# gt-jtx-m32-ver1_0.net
KiCad netlist of a schematic drawn in EAGLE
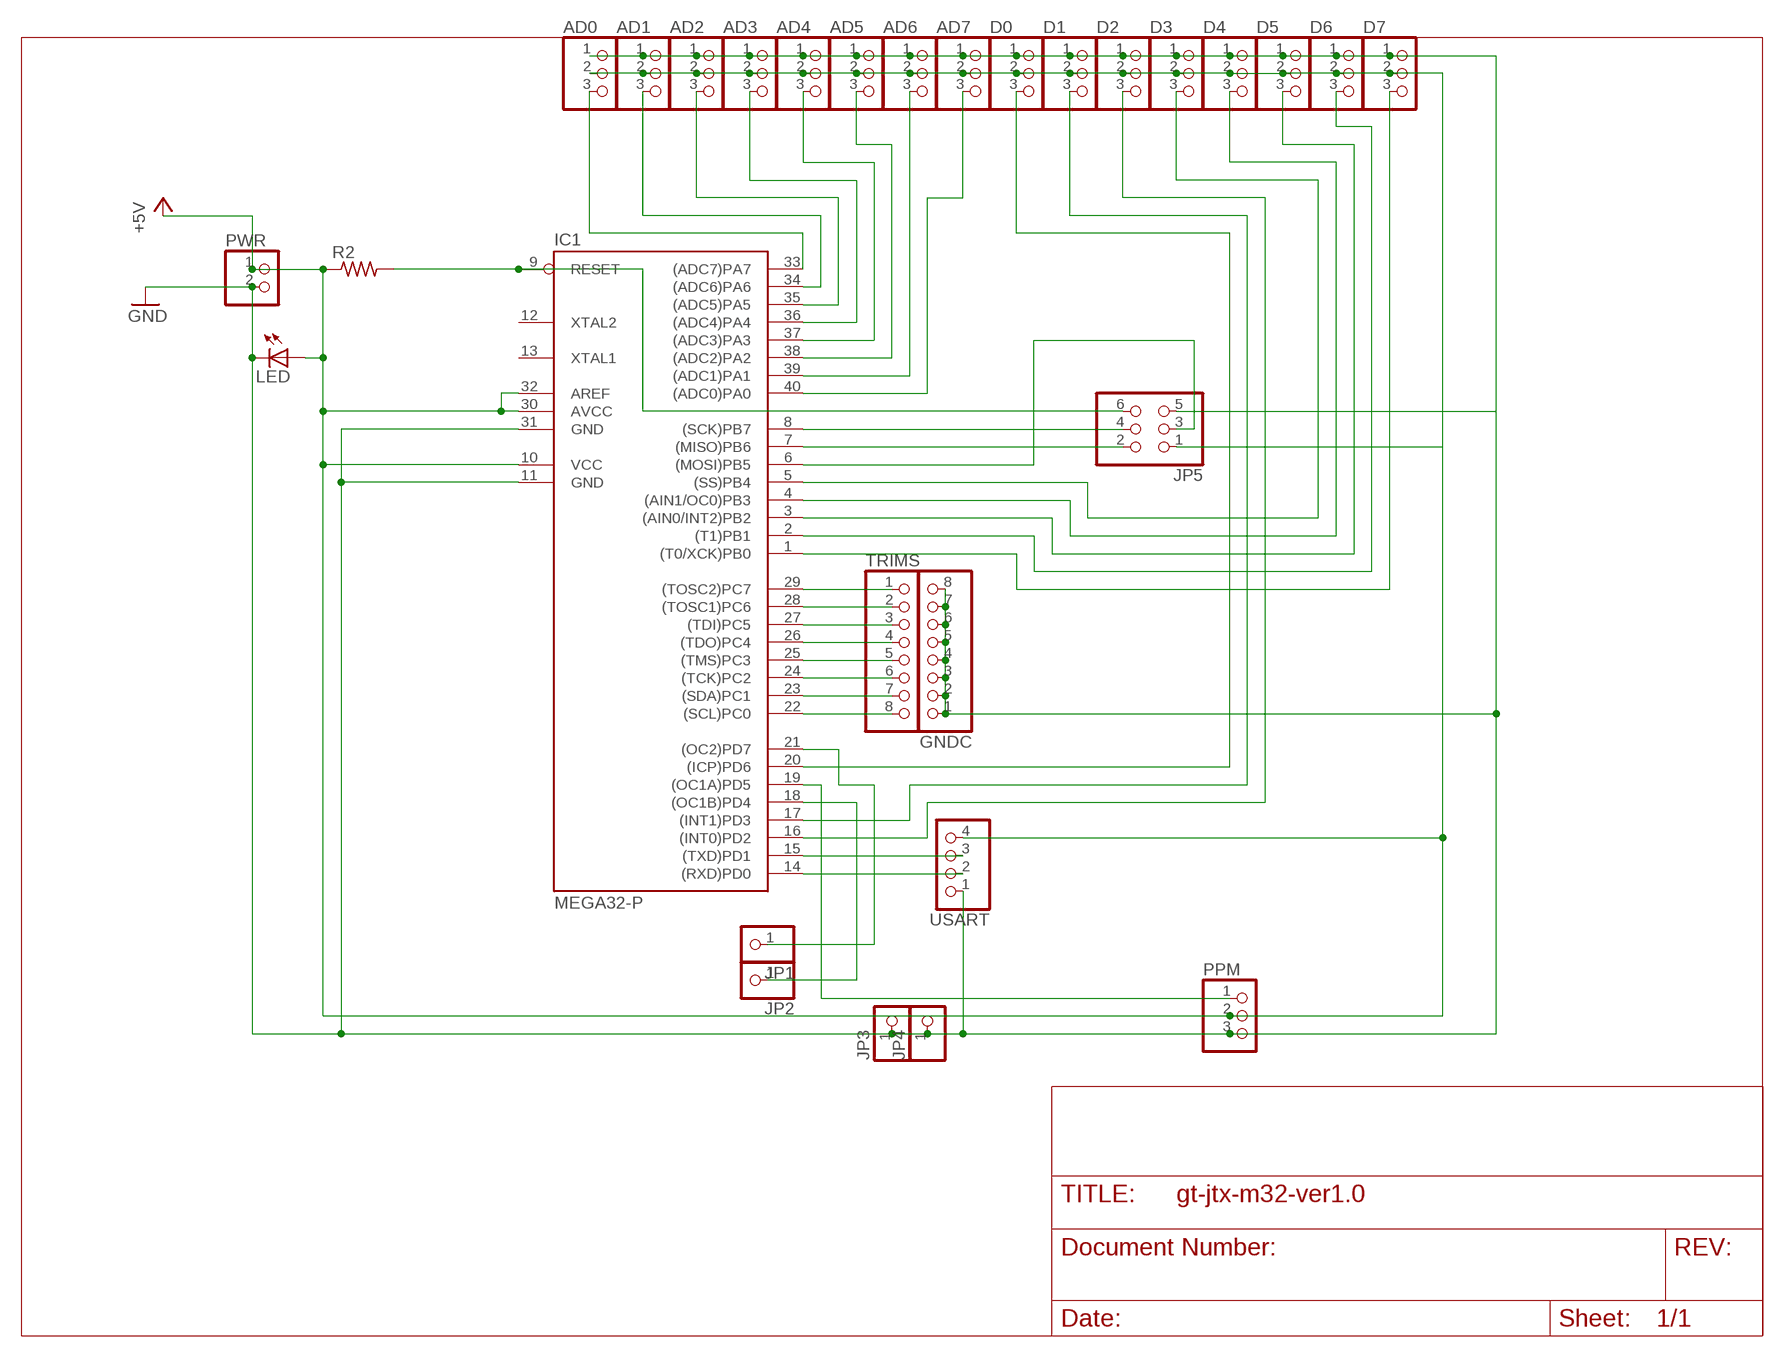
[diagram p0: schematic, sheet 1]

(export (version "E")
  (design (tool "Eeschema 10.0.6"))
  (components
    (comp (ref "AD0")
      (value "PINHD-1X3")
      (footprint "eagle-import:1X03")
      (libsource (lib "eagle-import") (part "PINHD-1X3"))
    )
    (comp (ref "AD1")
      (value "PINHD-1X3")
      (footprint "eagle-import:1X03")
      (libsource (lib "eagle-import") (part "PINHD-1X3"))
    )
    (comp (ref "AD2")
      (value "PINHD-1X3")
      (footprint "eagle-import:1X03")
      (libsource (lib "eagle-import") (part "PINHD-1X3"))
    )
    (comp (ref "AD3")
      (value "PINHD-1X3")
      (footprint "eagle-import:1X03")
      (libsource (lib "eagle-import") (part "PINHD-1X3"))
    )
    (comp (ref "AD4")
      (value "PINHD-1X3")
      (footprint "eagle-import:1X03")
      (libsource (lib "eagle-import") (part "PINHD-1X3"))
    )
    (comp (ref "AD5")
      (value "PINHD-1X3")
      (footprint "eagle-import:1X03")
      (libsource (lib "eagle-import") (part "PINHD-1X3"))
    )
    (comp (ref "AD6")
      (value "PINHD-1X3")
      (footprint "eagle-import:1X03")
      (libsource (lib "eagle-import") (part "PINHD-1X3"))
    )
    (comp (ref "AD7")
      (value "PINHD-1X3")
      (footprint "eagle-import:1X03")
      (libsource (lib "eagle-import") (part "PINHD-1X3"))
    )
    (comp (ref "D0")
      (value "PINHD-1X3")
      (footprint "eagle-import:1X03")
      (libsource (lib "eagle-import") (part "PINHD-1X3"))
    )
    (comp (ref "D1")
      (value "PINHD-1X3")
      (footprint "eagle-import:1X03")
      (libsource (lib "eagle-import") (part "PINHD-1X3"))
    )
    (comp (ref "D2")
      (value "PINHD-1X3")
      (footprint "eagle-import:1X03")
      (libsource (lib "eagle-import") (part "PINHD-1X3"))
    )
    (comp (ref "D3")
      (value "PINHD-1X3")
      (footprint "eagle-import:1X03")
      (libsource (lib "eagle-import") (part "PINHD-1X3"))
    )
    (comp (ref "D4")
      (value "PINHD-1X3")
      (footprint "eagle-import:1X03")
      (libsource (lib "eagle-import") (part "PINHD-1X3"))
    )
    (comp (ref "D5")
      (value "PINHD-1X3")
      (footprint "eagle-import:1X03")
      (libsource (lib "eagle-import") (part "PINHD-1X3"))
    )
    (comp (ref "D6")
      (value "PINHD-1X3")
      (footprint "eagle-import:1X03")
      (libsource (lib "eagle-import") (part "PINHD-1X3"))
    )
    (comp (ref "D7")
      (value "PINHD-1X3")
      (footprint "eagle-import:1X03")
      (libsource (lib "eagle-import") (part "PINHD-1X3"))
    )
    (comp (ref "GNDC")
      (value "PINHD-1X8")
      (footprint "eagle-import:1X08")
      (libsource (lib "eagle-import") (part "PINHD-1X8"))
    )
    (comp (ref "IC1")
      (value "MEGA32-P")
      (footprint "eagle-import:DIL40")
      (fields (field (name "MPN") "ATMEGA32-16PU"))
      (libsource (lib "eagle-import") (part "MEGA32-P"))
    )
    (comp (ref "JP1")
      (value "PINHD-1X1")
      (footprint "eagle-import:1X01")
      (libsource (lib "eagle-import") (part "PINHD-1X1"))
    )
    (comp (ref "JP2")
      (value "PINHD-1X1")
      (footprint "eagle-import:1X01")
      (libsource (lib "eagle-import") (part "PINHD-1X1"))
    )
    (comp (ref "JP3")
      (value "PINHD-1X1")
      (footprint "eagle-import:1X01")
      (libsource (lib "eagle-import") (part "PINHD-1X1"))
    )
    (comp (ref "JP4")
      (value "PINHD-1X1")
      (footprint "eagle-import:1X01")
      (libsource (lib "eagle-import") (part "PINHD-1X1"))
    )
    (comp (ref "JP5")
      (value "PINHD-2X3")
      (footprint "eagle-import:2X03")
      (libsource (lib "eagle-import") (part "PINHD-2X3"))
    )
    (comp (ref "LED")
      (value "LED5MM")
      (footprint "eagle-import:LED5MM")
      (libsource (lib "eagle-import") (part "LED5MM"))
    )
    (comp (ref "PPM")
      (value "PINHD-1X3")
      (footprint "eagle-import:1X03")
      (libsource (lib "eagle-import") (part "PINHD-1X3"))
    )
    (comp (ref "PWR")
      (value "PINHD-1X2")
      (footprint "eagle-import:1X02")
      (libsource (lib "eagle-import") (part "PINHD-1X2"))
    )
    (comp (ref "R2")
      (value "R-US_0204/2V")
      (footprint "eagle-import:0204V")
      (libsource (lib "eagle-import") (part "R-US_0204/2V"))
    )
    (comp (ref "TRIMS")
      (value "PINHD-1X8")
      (footprint "eagle-import:1X08")
      (libsource (lib "eagle-import") (part "PINHD-1X8"))
    )
    (comp (ref "USART")
      (value "PINHD-1X4")
      (footprint "eagle-import:1X04")
      (libsource (lib "eagle-import") (part "PINHD-1X4"))
    )
  )
  (nets
    (net (code "1") (name "+5V") (class "Default")
      (node (ref "AD0") (pin "2") (pinfunction "2_2") (pintype "passive"))
      (node (ref "AD1") (pin "2") (pinfunction "2_2") (pintype "passive"))
      (node (ref "AD2") (pin "2") (pinfunction "2_2") (pintype "passive"))
      (node (ref "AD3") (pin "2") (pinfunction "2_2") (pintype "passive"))
      (node (ref "AD4") (pin "2") (pinfunction "2_2") (pintype "passive"))
      (node (ref "AD5") (pin "2") (pinfunction "2_2") (pintype "passive"))
      (node (ref "AD6") (pin "2") (pinfunction "2_2") (pintype "passive"))
      (node (ref "AD7") (pin "2") (pinfunction "2_2") (pintype "passive"))
      (node (ref "D0") (pin "2") (pinfunction "2_2") (pintype "passive"))
      (node (ref "D1") (pin "2") (pinfunction "2_2") (pintype "passive"))
      (node (ref "D2") (pin "2") (pinfunction "2_2") (pintype "passive"))
      (node (ref "D3") (pin "2") (pinfunction "2_2") (pintype "passive"))
      (node (ref "D4") (pin "2") (pinfunction "2_2") (pintype "passive"))
      (node (ref "D5") (pin "2") (pinfunction "2_2") (pintype "passive"))
      (node (ref "D6") (pin "2") (pinfunction "2_2") (pintype "passive"))
      (node (ref "D7") (pin "2") (pinfunction "2_2") (pintype "passive"))
      (node (ref "IC1") (pin "10") (pinfunction "VCC_10") (pintype "power_in"))
      (node (ref "IC1") (pin "30") (pinfunction "AVCC_30") (pintype "power_in"))
      (node (ref "IC1") (pin "32") (pinfunction "AREF_32") (pintype "passive"))
      (node (ref "JP5") (pin "1") (pinfunction "1_1") (pintype "passive"))
      (node (ref "LED") (pin "A") (pinfunction "A_A") (pintype "passive"))
      (node (ref "PPM") (pin "2") (pinfunction "2_2") (pintype "passive"))
      (node (ref "PWR") (pin "1") (pinfunction "1_1") (pintype "passive"))
      (node (ref "R2") (pin "1") (pinfunction "1_1") (pintype "passive"))
      (node (ref "USART") (pin "4") (pinfunction "4_4") (pintype "passive"))
    )
    (net (code "2") (name "GND") (class "Default")
      (node (ref "AD0") (pin "1") (pinfunction "1_1") (pintype "passive"))
      (node (ref "AD1") (pin "1") (pinfunction "1_1") (pintype "passive"))
      (node (ref "AD2") (pin "1") (pinfunction "1_1") (pintype "passive"))
      (node (ref "AD3") (pin "1") (pinfunction "1_1") (pintype "passive"))
      (node (ref "AD4") (pin "1") (pinfunction "1_1") (pintype "passive"))
      (node (ref "AD5") (pin "1") (pinfunction "1_1") (pintype "passive"))
      (node (ref "AD6") (pin "1") (pinfunction "1_1") (pintype "passive"))
      (node (ref "AD7") (pin "1") (pinfunction "1_1") (pintype "passive"))
      (node (ref "D0") (pin "1") (pinfunction "1_1") (pintype "passive"))
      (node (ref "D1") (pin "1") (pinfunction "1_1") (pintype "passive"))
      (node (ref "D2") (pin "1") (pinfunction "1_1") (pintype "passive"))
      (node (ref "D3") (pin "1") (pinfunction "1_1") (pintype "passive"))
      (node (ref "D4") (pin "1") (pinfunction "1_1") (pintype "passive"))
      (node (ref "D5") (pin "1") (pinfunction "1_1") (pintype "passive"))
      (node (ref "D6") (pin "1") (pinfunction "1_1") (pintype "passive"))
      (node (ref "D7") (pin "1") (pinfunction "1_1") (pintype "passive"))
      (node (ref "GNDC") (pin "1") (pinfunction "1_1") (pintype "passive"))
      (node (ref "GNDC") (pin "2") (pinfunction "2_2") (pintype "passive"))
      (node (ref "GNDC") (pin "3") (pinfunction "3_3") (pintype "passive"))
      (node (ref "GNDC") (pin "4") (pinfunction "4_4") (pintype "passive"))
      (node (ref "GNDC") (pin "5") (pinfunction "5_5") (pintype "passive"))
      (node (ref "GNDC") (pin "6") (pinfunction "6_6") (pintype "passive"))
      (node (ref "GNDC") (pin "7") (pinfunction "7_7") (pintype "passive"))
      (node (ref "GNDC") (pin "8") (pinfunction "8_8") (pintype "passive"))
      (node (ref "IC1") (pin "11") (pinfunction "GND_11") (pintype "power_in"))
      (node (ref "IC1") (pin "31") (pinfunction "GND_31") (pintype "power_in"))
      (node (ref "JP3") (pin "1") (pinfunction "1_1") (pintype "passive"))
      (node (ref "JP4") (pin "1") (pinfunction "1_1") (pintype "passive"))
      (node (ref "JP5") (pin "5") (pinfunction "5_5") (pintype "passive"))
      (node (ref "LED") (pin "K") (pinfunction "C_K") (pintype "passive"))
      (node (ref "PPM") (pin "3") (pinfunction "3_3") (pintype "passive"))
      (node (ref "PWR") (pin "2") (pinfunction "2_2") (pintype "passive"))
      (node (ref "USART") (pin "1") (pinfunction "1_1") (pintype "passive"))
    )
    (net (code "3") (name "Net-(IC1-(ADC0)PA0)") (class "Default")
      (node (ref "AD7") (pin "3") (pinfunction "3_3") (pintype "passive"))
      (node (ref "IC1") (pin "40") (pinfunction "(ADC0)PA0_40") (pintype "bidirectional"))
    )
    (net (code "4") (name "Net-(IC1-(ADC1)PA1)") (class "Default")
      (node (ref "AD6") (pin "3") (pinfunction "3_3") (pintype "passive"))
      (node (ref "IC1") (pin "39") (pinfunction "(ADC1)PA1_39") (pintype "bidirectional"))
    )
    (net (code "5") (name "Net-(IC1-(ADC2)PA2)") (class "Default")
      (node (ref "AD5") (pin "3") (pinfunction "3_3") (pintype "passive"))
      (node (ref "IC1") (pin "38") (pinfunction "(ADC2)PA2_38") (pintype "bidirectional"))
    )
    (net (code "6") (name "Net-(IC1-(ADC3)PA3)") (class "Default")
      (node (ref "AD4") (pin "3") (pinfunction "3_3") (pintype "passive"))
      (node (ref "IC1") (pin "37") (pinfunction "(ADC3)PA3_37") (pintype "bidirectional"))
    )
    (net (code "7") (name "Net-(IC1-(ADC4)PA4)") (class "Default")
      (node (ref "AD3") (pin "3") (pinfunction "3_3") (pintype "passive"))
      (node (ref "IC1") (pin "36") (pinfunction "(ADC4)PA4_36") (pintype "bidirectional"))
    )
    (net (code "8") (name "Net-(IC1-(ADC5)PA5)") (class "Default")
      (node (ref "AD2") (pin "3") (pinfunction "3_3") (pintype "passive"))
      (node (ref "IC1") (pin "35") (pinfunction "(ADC5)PA5_35") (pintype "bidirectional"))
    )
    (net (code "9") (name "Net-(IC1-(ADC6)PA6)") (class "Default")
      (node (ref "AD1") (pin "3") (pinfunction "3_3") (pintype "passive"))
      (node (ref "IC1") (pin "34") (pinfunction "(ADC6)PA6_34") (pintype "bidirectional"))
    )
    (net (code "10") (name "Net-(IC1-(ADC7)PA7)") (class "Default")
      (node (ref "AD0") (pin "3") (pinfunction "3_3") (pintype "passive"))
      (node (ref "IC1") (pin "33") (pinfunction "(ADC7)PA7_33") (pintype "bidirectional"))
    )
    (net (code "11") (name "Net-(IC1-(AIN0{slash}INT2)PB2)") (class "Default")
      (node (ref "D5") (pin "3") (pinfunction "3_3") (pintype "passive"))
      (node (ref "IC1") (pin "3") (pinfunction "(AIN0/INT2)PB2_3") (pintype "bidirectional"))
    )
    (net (code "12") (name "Net-(IC1-(AIN1{slash}OC0)PB3)") (class "Default")
      (node (ref "D4") (pin "3") (pinfunction "3_3") (pintype "passive"))
      (node (ref "IC1") (pin "4") (pinfunction "(AIN1/OC0)PB3_4") (pintype "bidirectional"))
    )
    (net (code "13") (name "Net-(IC1-(ICP)PD6)") (class "Default")
      (node (ref "D0") (pin "3") (pinfunction "3_3") (pintype "passive"))
      (node (ref "IC1") (pin "20") (pinfunction "(ICP)PD6_20") (pintype "bidirectional"))
    )
    (net (code "14") (name "Net-(IC1-(INT0)PD2)") (class "Default")
      (node (ref "D2") (pin "3") (pinfunction "3_3") (pintype "passive"))
      (node (ref "IC1") (pin "16") (pinfunction "(INT0)PD2_16") (pintype "bidirectional"))
    )
    (net (code "15") (name "Net-(IC1-(INT1)PD3)") (class "Default")
      (node (ref "D1") (pin "3") (pinfunction "3_3") (pintype "passive"))
      (node (ref "IC1") (pin "17") (pinfunction "(INT1)PD3_17") (pintype "bidirectional"))
    )
    (net (code "16") (name "Net-(IC1-(MISO)PB6)") (class "Default")
      (node (ref "IC1") (pin "7") (pinfunction "(MISO)PB6_7") (pintype "bidirectional"))
      (node (ref "JP5") (pin "2") (pinfunction "2_2") (pintype "passive"))
    )
    (net (code "17") (name "Net-(IC1-(MOSI)PB5)") (class "Default")
      (node (ref "IC1") (pin "6") (pinfunction "(MOSI)PB5_6") (pintype "bidirectional"))
      (node (ref "JP5") (pin "3") (pinfunction "3_3") (pintype "passive"))
    )
    (net (code "18") (name "Net-(IC1-(OC1A)PD5)") (class "Default")
      (node (ref "IC1") (pin "19") (pinfunction "(OC1A)PD5_19") (pintype "bidirectional"))
      (node (ref "PPM") (pin "1") (pinfunction "1_1") (pintype "passive"))
    )
    (net (code "19") (name "Net-(IC1-(OC1B)PD4)") (class "Default")
      (node (ref "IC1") (pin "18") (pinfunction "(OC1B)PD4_18") (pintype "bidirectional"))
      (node (ref "JP2") (pin "1") (pinfunction "1_1") (pintype "passive"))
    )
    (net (code "20") (name "Net-(IC1-(OC2)PD7)") (class "Default")
      (node (ref "IC1") (pin "21") (pinfunction "(OC2)PD7_21") (pintype "bidirectional"))
      (node (ref "JP1") (pin "1") (pinfunction "1_1") (pintype "passive"))
    )
    (net (code "21") (name "Net-(IC1-(RXD)PD0)") (class "Default")
      (node (ref "IC1") (pin "14") (pinfunction "(RXD)PD0_14") (pintype "bidirectional"))
      (node (ref "USART") (pin "2") (pinfunction "2_2") (pintype "passive"))
    )
    (net (code "22") (name "Net-(IC1-(SCK)PB7)") (class "Default")
      (node (ref "IC1") (pin "8") (pinfunction "(SCK)PB7_8") (pintype "bidirectional"))
      (node (ref "JP5") (pin "4") (pinfunction "4_4") (pintype "passive"))
    )
    (net (code "23") (name "Net-(IC1-(SCL)PC0)") (class "Default")
      (node (ref "IC1") (pin "22") (pinfunction "(SCL)PC0_22") (pintype "bidirectional"))
      (node (ref "TRIMS") (pin "8") (pinfunction "8_8") (pintype "passive"))
    )
    (net (code "24") (name "Net-(IC1-(SDA)PC1)") (class "Default")
      (node (ref "IC1") (pin "23") (pinfunction "(SDA)PC1_23") (pintype "bidirectional"))
      (node (ref "TRIMS") (pin "7") (pinfunction "7_7") (pintype "passive"))
    )
    (net (code "25") (name "Net-(IC1-(SS)PB4)") (class "Default")
      (node (ref "D3") (pin "3") (pinfunction "3_3") (pintype "passive"))
      (node (ref "IC1") (pin "5") (pinfunction "(SS)PB4_5") (pintype "bidirectional"))
    )
    (net (code "26") (name "Net-(IC1-(T0{slash}XCK)PB0)") (class "Default")
      (node (ref "D7") (pin "3") (pinfunction "3_3") (pintype "passive"))
      (node (ref "IC1") (pin "1") (pinfunction "(T0/XCK)PB0_1") (pintype "bidirectional"))
    )
    (net (code "27") (name "Net-(IC1-(T1)PB1)") (class "Default")
      (node (ref "D6") (pin "3") (pinfunction "3_3") (pintype "passive"))
      (node (ref "IC1") (pin "2") (pinfunction "(T1)PB1_2") (pintype "bidirectional"))
    )
    (net (code "28") (name "Net-(IC1-(TCK)PC2)") (class "Default")
      (node (ref "IC1") (pin "24") (pinfunction "(TCK)PC2_24") (pintype "bidirectional"))
      (node (ref "TRIMS") (pin "6") (pinfunction "6_6") (pintype "passive"))
    )
    (net (code "29") (name "Net-(IC1-(TDI)PC5)") (class "Default")
      (node (ref "IC1") (pin "27") (pinfunction "(TDI)PC5_27") (pintype "bidirectional"))
      (node (ref "TRIMS") (pin "3") (pinfunction "3_3") (pintype "passive"))
    )
    (net (code "30") (name "Net-(IC1-(TDO)PC4)") (class "Default")
      (node (ref "IC1") (pin "26") (pinfunction "(TDO)PC4_26") (pintype "bidirectional"))
      (node (ref "TRIMS") (pin "4") (pinfunction "4_4") (pintype "passive"))
    )
    (net (code "31") (name "Net-(IC1-(TMS)PC3)") (class "Default")
      (node (ref "IC1") (pin "25") (pinfunction "(TMS)PC3_25") (pintype "bidirectional"))
      (node (ref "TRIMS") (pin "5") (pinfunction "5_5") (pintype "passive"))
    )
    (net (code "32") (name "Net-(IC1-(TOSC1)PC6)") (class "Default")
      (node (ref "IC1") (pin "28") (pinfunction "(TOSC1)PC6_28") (pintype "bidirectional"))
      (node (ref "TRIMS") (pin "2") (pinfunction "2_2") (pintype "passive"))
    )
    (net (code "33") (name "Net-(IC1-(TOSC2)PC7)") (class "Default")
      (node (ref "IC1") (pin "29") (pinfunction "(TOSC2)PC7_29") (pintype "bidirectional"))
      (node (ref "TRIMS") (pin "1") (pinfunction "1_1") (pintype "passive"))
    )
    (net (code "34") (name "Net-(IC1-(TXD)PD1)") (class "Default")
      (node (ref "IC1") (pin "15") (pinfunction "(TXD)PD1_15") (pintype "bidirectional"))
      (node (ref "USART") (pin "3") (pinfunction "3_3") (pintype "passive"))
    )
    (net (code "35") (name "Net-(IC1-RESET)") (class "Default")
      (node (ref "IC1") (pin "9") (pinfunction "RESET_9") (pintype "input"))
      (node (ref "JP5") (pin "6") (pinfunction "6_6") (pintype "passive"))
      (node (ref "R2") (pin "2") (pinfunction "2_2") (pintype "passive"))
    )
    (net (code "36") (name "unconnected-(IC1-XTAL1-Pad13)") (class "Default")
      (node (ref "IC1") (pin "13") (pinfunction "XTAL1_13") (pintype "bidirectional"))
    )
    (net (code "37") (name "unconnected-(IC1-XTAL2-Pad12)") (class "Default")
      (node (ref "IC1") (pin "12") (pinfunction "XTAL2_12") (pintype "bidirectional"))
    )
  )
)
